# SWD_Breakout.net
KiCad netlist of a schematic drawn in Altium Designer
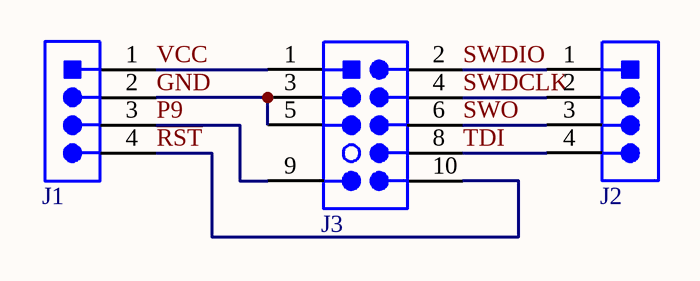
[diagram p0: SWD Breakout.SchDoc]

(export (version "E")
  (design (tool "Eeschema 10.0.6"))
  (components
    (comp (ref "J1")
      (value "4 contacts Male header")
      (footprint "61300411121")
      (description "Connector Male Header 1X4 vertical 4contacts 0.100in pitch 30uin Gold finish TH")
      (fields (field (name "MANUFACTURER") "Würth Elektronik"))
      (libsource (lib "Connectors") (part "Header 1X4"))
    )
    (comp (ref "J2")
      (value "4 contacts Male header")
      (footprint "61300411121")
      (description "Connector Male Header 1X4 vertical 4contacts 0.100in pitch 30uin Gold finish TH")
      (fields (field (name "MANUFACTURER") "Würth Elektronik"))
      (libsource (lib "") (part "Header 1X4_1"))
    )
    (comp (ref "J3")
      (value "Cortex Debug, 0.050\" 10 Pin")
      (footprint "FTSH-105-01-F-DV-007-K PLUGIN")
      (description "10 Pin Shrouded Header, 0.050\", Key Pin 7")
      (fields (field (name "MANUFACTURER") "Samtech"))
      (libsource (lib "Connectors") (part "Cortex Debug"))
    )
  )
  (nets
    (net (code "1") (name "/GND") (class "Default")
      (node (ref "J1") (pin "2") (pinfunction "2_2") (pintype "passive"))
      (node (ref "J3") (pin "3") (pinfunction "GND_3") (pintype "power_in"))
      (node (ref "J3") (pin "5") (pinfunction "GND_5") (pintype "power_in"))
    )
    (net (code "2") (name "/P9") (class "Default")
      (node (ref "J1") (pin "3") (pinfunction "3_3") (pintype "passive"))
      (node (ref "J3") (pin "9") (pinfunction "GNDDetect_9") (pintype "power_in"))
    )
    (net (code "3") (name "/RST") (class "Default")
      (node (ref "J1") (pin "4") (pinfunction "4_4") (pintype "passive"))
      (node (ref "J3") (pin "10") (pinfunction "RESET_10") (pintype "passive"))
    )
    (net (code "4") (name "/SWDCLK") (class "Default")
      (node (ref "J2") (pin "2") (pinfunction "2_2") (pintype "passive"))
      (node (ref "J3") (pin "4") (pinfunction "SWDCLK/TCK_4") (pintype "passive"))
    )
    (net (code "5") (name "/SWDIO") (class "Default")
      (node (ref "J2") (pin "1") (pinfunction "1_1") (pintype "passive"))
      (node (ref "J3") (pin "2") (pinfunction "SWDIO/TMS_2") (pintype "passive"))
    )
    (net (code "6") (name "/SWO") (class "Default")
      (node (ref "J2") (pin "3") (pinfunction "3_3") (pintype "passive"))
      (node (ref "J3") (pin "6") (pinfunction "SWO/TDO_6") (pintype "passive"))
    )
    (net (code "7") (name "/TDI") (class "Default")
      (node (ref "J2") (pin "4") (pinfunction "4_4") (pintype "passive"))
      (node (ref "J3") (pin "8") (pinfunction "NC/TDI_8") (pintype "passive"))
    )
    (net (code "8") (name "/VCC") (class "Default")
      (node (ref "J1") (pin "1") (pinfunction "1_1") (pintype "passive"))
      (node (ref "J3") (pin "1") (pinfunction "VCC_1") (pintype "power_in"))
    )
  )
)
